# CENTRALLEDS.net
KiCad netlist of a schematic drawn in Altium Designer
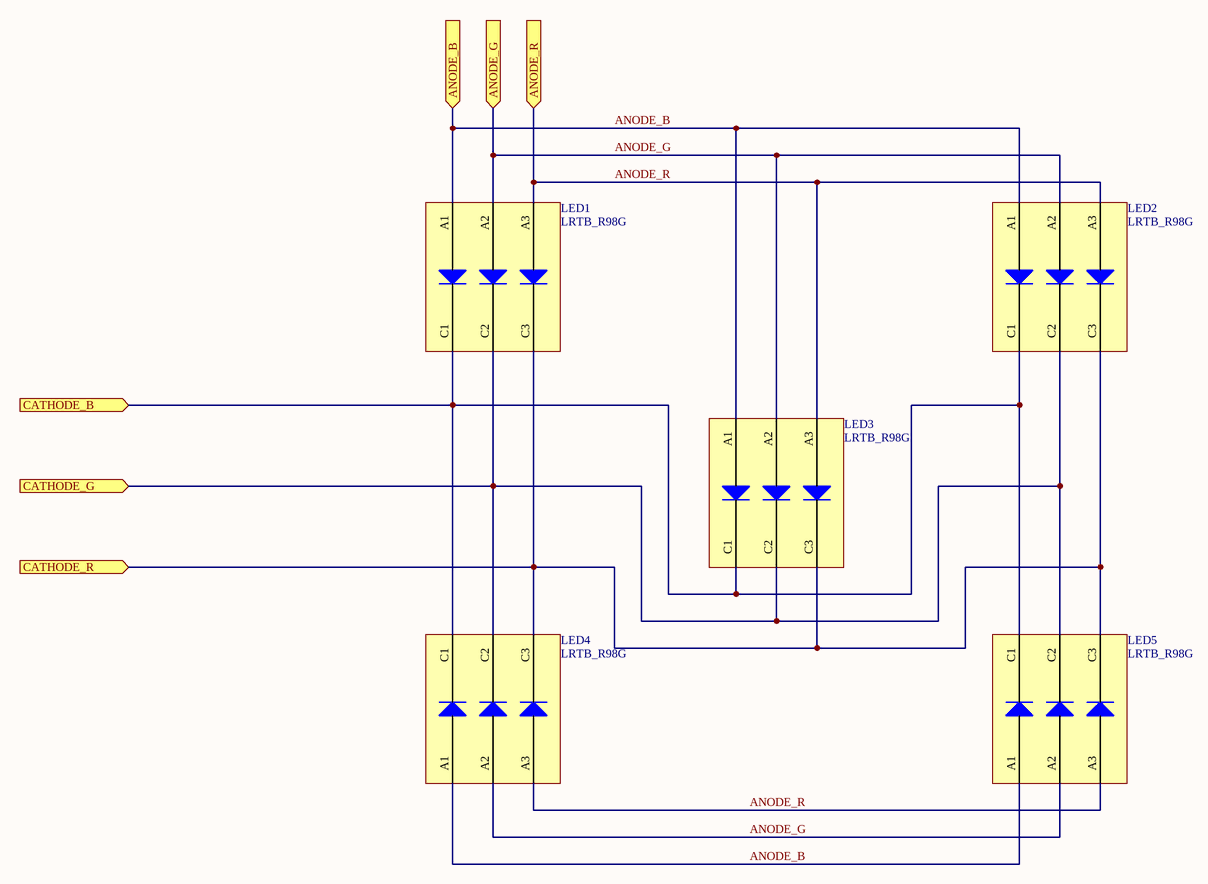
[diagram p0: CENTRALLEDS.SchDoc]

(export (version "E")
  (design (tool "Eeschema 10.0.6"))
  (components
    (comp (ref "LED1")
      (value "LRTB_R98G")
      (footprint "LRTB_R98G")
      (description "IC RGB LED OSRAM")
      (fields (field (name "MANUFACTURER") "OSRAM"))
      (libsource (lib "SmartHalo_Symbols") (part "LRTB_R98G"))
    )
    (comp (ref "LED2")
      (value "LRTB_R98G")
      (footprint "LRTB_R98G")
      (description "IC RGB LED OSRAM")
      (fields (field (name "MANUFACTURER") "OSRAM"))
      (libsource (lib "SmartHalo_Symbols") (part "LRTB_R98G"))
    )
    (comp (ref "LED3")
      (value "LRTB_R98G")
      (footprint "LRTB_R98G")
      (description "IC RGB LED OSRAM")
      (fields (field (name "MANUFACTURER") "OSRAM"))
      (libsource (lib "SmartHalo_Symbols") (part "LRTB_R98G"))
    )
    (comp (ref "LED4")
      (value "LRTB_R98G")
      (footprint "LRTB_R98G")
      (description "IC RGB LED OSRAM")
      (fields (field (name "MANUFACTURER") "OSRAM"))
      (libsource (lib "") (part "LRTB_R98G_1"))
    )
    (comp (ref "LED5")
      (value "LRTB_R98G")
      (footprint "LRTB_R98G")
      (description "IC RGB LED OSRAM")
      (fields (field (name "MANUFACTURER") "OSRAM"))
      (libsource (lib "") (part "LRTB_R98G_1"))
    )
  )
  (nets
    (net (code "1") (name "/ANODE_B") (class "Default")
      (node (ref "LED1") (pin "A1") (pinfunction "Anode_Blue_A1") (pintype "passive"))
      (node (ref "LED2") (pin "A1") (pinfunction "Anode_Blue_A1") (pintype "passive"))
      (node (ref "LED3") (pin "A1") (pinfunction "Anode_Blue_A1") (pintype "passive"))
      (node (ref "LED4") (pin "A1") (pinfunction "Anode_Blue_A1") (pintype "passive"))
      (node (ref "LED5") (pin "A1") (pinfunction "Anode_Blue_A1") (pintype "passive"))
    )
    (net (code "2") (name "/ANODE_G") (class "Default")
      (node (ref "LED1") (pin "A2") (pinfunction "Anode_Green_A2") (pintype "passive"))
      (node (ref "LED2") (pin "A2") (pinfunction "Anode_Green_A2") (pintype "passive"))
      (node (ref "LED3") (pin "A2") (pinfunction "Anode_Green_A2") (pintype "passive"))
      (node (ref "LED4") (pin "A2") (pinfunction "Anode_Green_A2") (pintype "passive"))
      (node (ref "LED5") (pin "A2") (pinfunction "Anode_Green_A2") (pintype "passive"))
    )
    (net (code "3") (name "/ANODE_R") (class "Default")
      (node (ref "LED1") (pin "A3") (pinfunction "Anode_Red_A3") (pintype "passive"))
      (node (ref "LED2") (pin "A3") (pinfunction "Anode_Red_A3") (pintype "passive"))
      (node (ref "LED3") (pin "A3") (pinfunction "Anode_Red_A3") (pintype "passive"))
      (node (ref "LED4") (pin "A3") (pinfunction "Anode_Red_A3") (pintype "passive"))
      (node (ref "LED5") (pin "A3") (pinfunction "Anode_Red_A3") (pintype "passive"))
    )
    (net (code "4") (name "/CATHODE_B") (class "Default")
      (node (ref "LED1") (pin "C1") (pinfunction "Cathode_Blue_C1") (pintype "passive"))
      (node (ref "LED2") (pin "C1") (pinfunction "Cathode_Blue_C1") (pintype "passive"))
      (node (ref "LED3") (pin "C1") (pinfunction "Cathode_Blue_C1") (pintype "passive"))
      (node (ref "LED4") (pin "C1") (pinfunction "Cathode_Blue_C1") (pintype "passive"))
      (node (ref "LED5") (pin "C1") (pinfunction "Cathode_Blue_C1") (pintype "passive"))
    )
    (net (code "5") (name "/CATHODE_G") (class "Default")
      (node (ref "LED1") (pin "C2") (pinfunction "Cathode_Green_C2") (pintype "passive"))
      (node (ref "LED2") (pin "C2") (pinfunction "Cathode_Green_C2") (pintype "passive"))
      (node (ref "LED3") (pin "C2") (pinfunction "Cathode_Green_C2") (pintype "passive"))
      (node (ref "LED4") (pin "C2") (pinfunction "Cathode_Green_C2") (pintype "passive"))
      (node (ref "LED5") (pin "C2") (pinfunction "Cathode_Green_C2") (pintype "passive"))
    )
    (net (code "6") (name "/CATHODE_R") (class "Default")
      (node (ref "LED1") (pin "C3") (pinfunction "Cathode_Red_C3") (pintype "passive"))
      (node (ref "LED2") (pin "C3") (pinfunction "Cathode_Red_C3") (pintype "passive"))
      (node (ref "LED3") (pin "C3") (pinfunction "Cathode_Red_C3") (pintype "passive"))
      (node (ref "LED4") (pin "C3") (pinfunction "Cathode_Red_C3") (pintype "passive"))
      (node (ref "LED5") (pin "C3") (pinfunction "Cathode_Red_C3") (pintype "passive"))
    )
  )
)
